# 05_-_Camera_Interface_2.net
KiCad netlist of a schematic drawn in Altium Designer
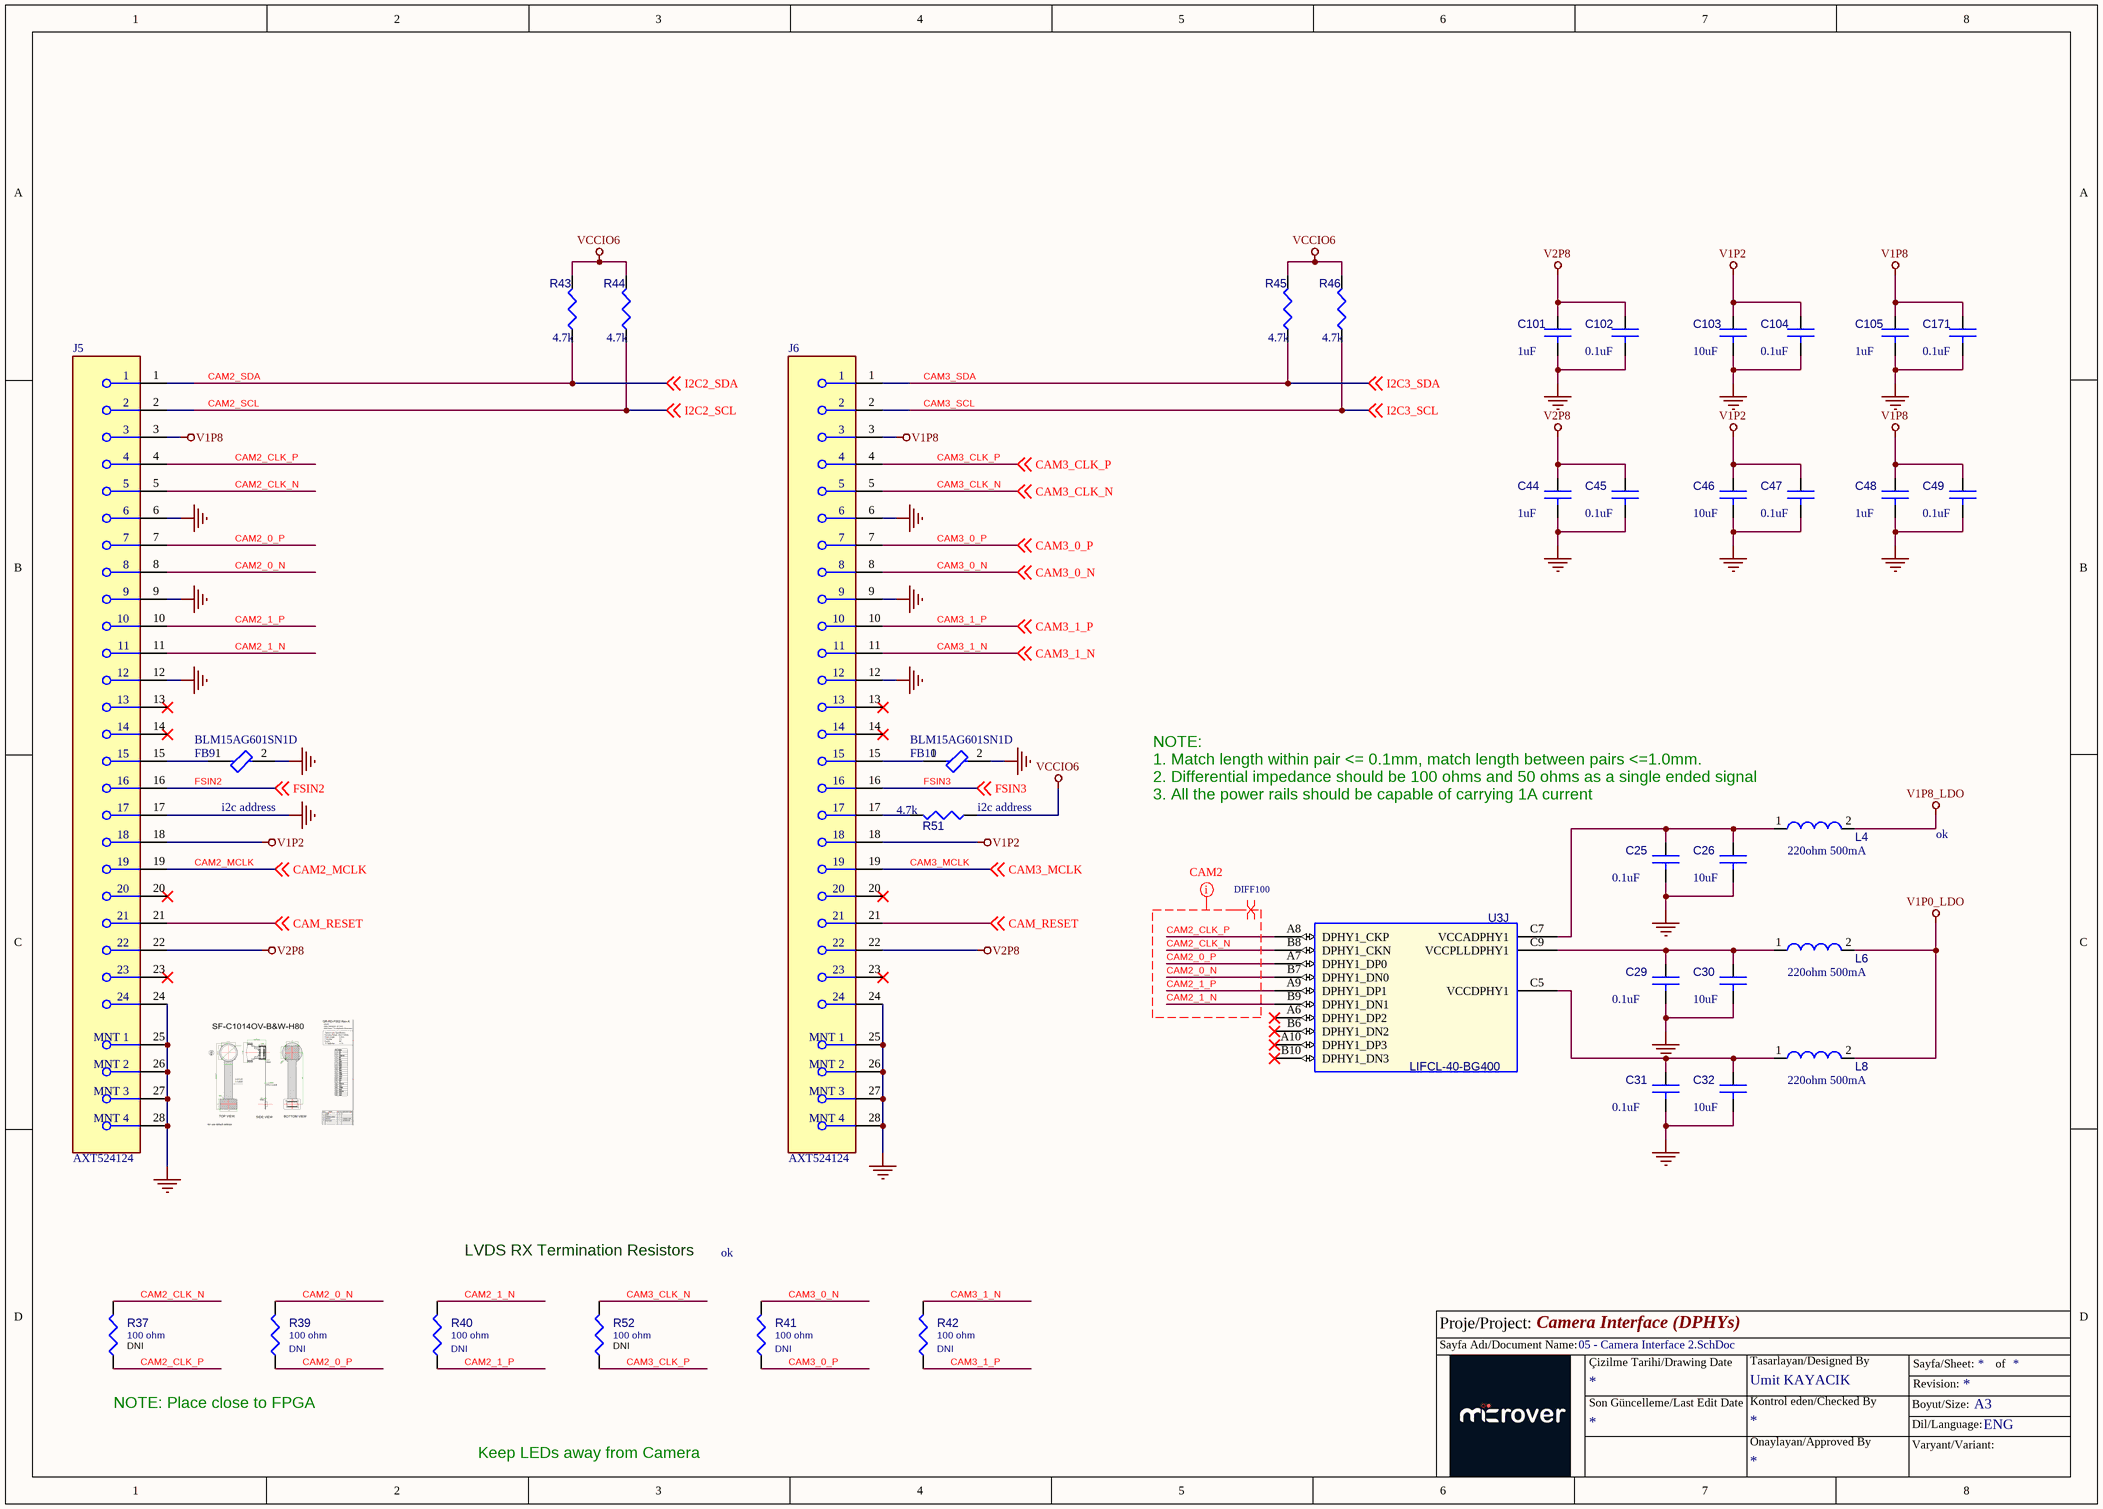
[diagram p0: 05 - Camera Interface 2.SchDoc]

(export (version "E")
  (design (tool "Eeschema 10.0.6"))
  (components
    (comp (ref "C25")
      (value "0.1uF")
      (footprint "C0201")
      (description "CAP CER 0.1UF 25V 10% X5R 0201")
      (fields
        (field (name "MANUFACTURER") "Murata")
        (field (name "MANUFACTURER PART NUMBER") "GRM033R61E104KE14J")
      )
      (libsource (lib "*") (part "0u1_0402"))
    )
    (comp (ref "C26")
      (value "10uF")
      (footprint "C0402")
      (description "CAP CER 10UF 10V X5R 0402")
      (fields
        (field (name "MANUFACTURER") "Samsung")
        (field (name "MANUFACTURER PART NUMBER") "CL05A106MP8NUB8")
      )
      (libsource (lib "*") (part "10uF_0603"))
    )
    (comp (ref "C29")
      (value "0.1uF")
      (footprint "C0201")
      (description "CAP CER 0.1UF 25V 10% X5R 0201")
      (fields
        (field (name "MANUFACTURER") "Murata")
        (field (name "MANUFACTURER PART NUMBER") "GRM033R61E104KE14J")
      )
      (libsource (lib "*") (part "0u1_0402"))
    )
    (comp (ref "C30")
      (value "10uF")
      (footprint "C0402")
      (description "CAP CER 10UF 10V X5R 0402")
      (fields
        (field (name "MANUFACTURER") "Samsung")
        (field (name "MANUFACTURER PART NUMBER") "CL05A106MP8NUB8")
      )
      (libsource (lib "*") (part "10uF_0603"))
    )
    (comp (ref "C31")
      (value "0.1uF")
      (footprint "C0201")
      (description "CAP CER 0.1UF 25V 10% X5R 0201")
      (fields
        (field (name "MANUFACTURER") "Murata")
        (field (name "MANUFACTURER PART NUMBER") "GRM033R61E104KE14J")
      )
      (libsource (lib "*") (part "0u1_0402"))
    )
    (comp (ref "C32")
      (value "10uF")
      (footprint "C0402")
      (description "CAP CER 10UF 10V X5R 0402")
      (fields
        (field (name "MANUFACTURER") "Samsung")
        (field (name "MANUFACTURER PART NUMBER") "CL05A106MP8NUB8")
      )
      (libsource (lib "*") (part "10uF_0603"))
    )
    (comp (ref "C44")
      (value "1uF")
      (footprint "C0603")
      (description "CAP CECAP CER 10UF 10V X5R 20% 0603")
      (fields
        (field (name "MANUFACTURER") "Taiyo Yuden")
        (field (name "MANUFACTURER PART NUMBER") "LMK107BJ106MALTD")
      )
      (libsource (lib "*") (part "10uF_0603"))
    )
    (comp (ref "C45")
      (value "0.1uF")
      (footprint "C0201")
      (description "CAP CER 0.1UF 25V 10% X5R 0201")
      (fields
        (field (name "MANUFACTURER") "Murata")
        (field (name "MANUFACTURER PART NUMBER") "GRM033R61E104KE14J")
      )
      (libsource (lib "*") (part "0u1_0402"))
    )
    (comp (ref "C46")
      (value "10uF")
      (footprint "C0603")
      (description "CAP CECAP CER 10UF 10V X5R 20% 0603")
      (fields
        (field (name "MANUFACTURER") "Taiyo Yuden")
        (field (name "MANUFACTURER PART NUMBER") "LMK107BJ106MALTD")
      )
      (libsource (lib "*") (part "10uF_0603"))
    )
    (comp (ref "C47")
      (value "0.1uF")
      (footprint "C0201")
      (description "CAP CER 0.1UF 25V 10% X5R 0201")
      (fields
        (field (name "MANUFACTURER") "Murata")
        (field (name "MANUFACTURER PART NUMBER") "GRM033R61E104KE14J")
      )
      (libsource (lib "*") (part "0u1_0402"))
    )
    (comp (ref "C48")
      (value "1uF")
      (footprint "C0603")
      (description "CAP CECAP CER 10UF 10V X5R 20% 0603")
      (fields
        (field (name "MANUFACTURER") "Taiyo Yuden")
        (field (name "MANUFACTURER PART NUMBER") "LMK107BJ106MALTD")
      )
      (libsource (lib "*") (part "10uF_0603"))
    )
    (comp (ref "C49")
      (value "0.1uF")
      (footprint "C0201")
      (description "CAP CER 0.1UF 25V 10% X5R 0201")
      (fields
        (field (name "MANUFACTURER") "Murata")
        (field (name "MANUFACTURER PART NUMBER") "GRM033R61E104KE14J")
      )
      (libsource (lib "*") (part "0u1_0402"))
    )
    (comp (ref "C101")
      (value "1uF")
      (footprint "C0603")
      (description "CAP CECAP CER 10UF 10V X5R 20% 0603")
      (fields
        (field (name "MANUFACTURER") "Taiyo Yuden")
        (field (name "MANUFACTURER PART NUMBER") "LMK107BJ106MALTD")
      )
      (libsource (lib "*") (part "10uF_0603"))
    )
    (comp (ref "C102")
      (value "0.1uF")
      (footprint "C0201")
      (description "CAP CER 0.1UF 25V 10% X5R 0201")
      (fields
        (field (name "MANUFACTURER") "Murata")
        (field (name "MANUFACTURER PART NUMBER") "GRM033R61E104KE14J")
      )
      (libsource (lib "*") (part "0u1_0402"))
    )
    (comp (ref "C103")
      (value "10uF")
      (footprint "C0603")
      (description "CAP CECAP CER 10UF 10V X5R 20% 0603")
      (fields
        (field (name "MANUFACTURER") "Taiyo Yuden")
        (field (name "MANUFACTURER PART NUMBER") "LMK107BJ106MALTD")
      )
      (libsource (lib "*") (part "10uF_0603"))
    )
    (comp (ref "C104")
      (value "0.1uF")
      (footprint "C0201")
      (description "CAP CER 0.1UF 25V 10% X5R 0201")
      (fields
        (field (name "MANUFACTURER") "Murata")
        (field (name "MANUFACTURER PART NUMBER") "GRM033R61E104KE14J")
      )
      (libsource (lib "*") (part "0u1_0402"))
    )
    (comp (ref "C105")
      (value "1uF")
      (footprint "C0603")
      (description "CAP CECAP CER 10UF 10V X5R 20% 0603")
      (fields
        (field (name "MANUFACTURER") "Taiyo Yuden")
        (field (name "MANUFACTURER PART NUMBER") "LMK107BJ106MALTD")
      )
      (libsource (lib "*") (part "10uF_0603"))
    )
    (comp (ref "C171")
      (value "0.1uF")
      (footprint "C0201")
      (description "CAP CER 0.1UF 25V 10% X5R 0201")
      (fields
        (field (name "MANUFACTURER") "Murata")
        (field (name "MANUFACTURER PART NUMBER") "GRM033R61E104KE14J")
      )
      (libsource (lib "*") (part "0u1_0402"))
    )
    (comp (ref "FB9")
      (value "BLM15AG601SN1D")
      (footprint "FP-BLM15-0_05-MFG")
      (description "Chip Ferrite Bead, 0402, 600Ω @ 100MHz, 0.52Ω, 25%, 300mA")
      (fields (field (name "TOLERANCE") "25%"))
      (libsource (lib "Altium Content Vault") (part "5f30dd21d616792df468990f7003faa"))
    )
    (comp (ref "FB10")
      (value "BLM15AG601SN1D")
      (footprint "FP-BLM15-0_05-MFG")
      (description "Chip Ferrite Bead, 0402, 600Ω @ 100MHz, 0.52Ω, 25%, 300mA")
      (fields (field (name "TOLERANCE") "25%"))
      (libsource (lib "Altium Content Vault") (part "5f30dd21d616792df468990f7003faa"))
    )
    (comp (ref "J5")
      (value "AXT524124")
      (footprint "FP-AXT524124-MFG")
      (description "AXT524124 24 Position 0.4 mm Pitch Dual Row Board to Board Socket Narrow Pitch Connector")
      (libsource (lib "Chronos") (part "AXT524124"))
    )
    (comp (ref "J6")
      (value "AXT524124")
      (footprint "FP-AXT524124-MFG")
      (description "AXT524124 24 Position 0.4 mm Pitch Dual Row Board to Board Socket Narrow Pitch Connector")
      (libsource (lib "Chronos") (part "AXT524124"))
    )
    (comp (ref "L4")
      (value "220ohm 500mA")
      (footprint "FB0402")
      (description "FERRITE BEAD 600 OHM 0402 1LN")
      (fields
        (field (name "MANUFACTURER") "Murata")
        (field (name "MANUFACTURER PART NUMBER") "BLM15AX601SN1D")
      )
      (libsource (lib "*") (part "FB0603"))
    )
    (comp (ref "L6")
      (value "220ohm 500mA")
      (footprint "FB0402")
      (description "FERRITE BEAD 600 OHM 0402 1LN")
      (fields
        (field (name "MANUFACTURER") "Murata")
        (field (name "MANUFACTURER PART NUMBER") "BLM15AX601SN1D")
      )
      (libsource (lib "*") (part "FB0603"))
    )
    (comp (ref "L8")
      (value "220ohm 500mA")
      (footprint "FB0402")
      (description "FERRITE BEAD 600 OHM 0402 1LN")
      (fields
        (field (name "MANUFACTURER") "Murata")
        (field (name "MANUFACTURER PART NUMBER") "BLM15AX601SN1D")
      )
      (libsource (lib "*") (part "FB0603"))
    )
    (comp (ref "R37")
      (value "100 ohm")
      (footprint "R0201")
      (description "RES SMD 100 OHM 1% 1/20W 0201")
      (fields (field (name "MFG") "Yageo") (field (name "MANUFACTURER PART NUMBER") "RC0201FR-07100RL"))
      (libsource (lib "*") (part "RES_100K_1W16_0402_5P"))
    )
    (comp (ref "R39")
      (value "100 ohm")
      (footprint "R0201")
      (description "RES SMD 100 OHM 1% 1/20W 0201")
      (fields
        (field (name "MFG") "Yageo")
        (field (name "MANUFACTURER PART NUMBER") "RC0201FR-07100RL")
        (field (name "ASSY") "DNI")
      )
      (libsource (lib "*") (part "RES_100K_1W16_0402_5P"))
    )
    (comp (ref "R40")
      (value "100 ohm")
      (footprint "R0201")
      (description "RES SMD 100 OHM 1% 1/20W 0201")
      (fields
        (field (name "MFG") "Yageo")
        (field (name "MANUFACTURER PART NUMBER") "RC0201FR-07100RL")
        (field (name "ASSY") "DNI")
      )
      (libsource (lib "*") (part "RES_100K_1W16_0402_5P"))
    )
    (comp (ref "R41")
      (value "100 ohm")
      (footprint "R0201")
      (description "RES SMD 100 OHM 1% 1/20W 0201")
      (fields
        (field (name "MFG") "Yageo")
        (field (name "ASSY") "DNI")
        (field (name "MANUFACTURER PART NUMBER") "RC0201FR-07100RL")
      )
      (libsource (lib "*") (part "RES_100K_1W16_0402_5P"))
    )
    (comp (ref "R42")
      (value "100 ohm")
      (footprint "R0201")
      (description "RES SMD 100 OHM 1% 1/20W 0201")
      (fields
        (field (name "MFG") "Yageo")
        (field (name "ASSY") "DNI")
        (field (name "MANUFACTURER PART NUMBER") "RC0201FR-07100RL")
      )
      (libsource (lib "*") (part "RES_100K_1W16_0402_5P"))
    )
    (comp (ref "R43")
      (value "4.7k")
      (footprint "R0402")
      (description "RES SMD 2.2K OHM 1% 1/10W 0402")
      (fields
        (field (name "MANUFACTURER PART NUMBER") "ERJ-2RKF2201X")
        (field (name "MANUFACTURER") "Panasonic")
      )
      (libsource (lib "*") (part "5k1_0402"))
    )
    (comp (ref "R44")
      (value "4.7k")
      (footprint "R0402")
      (description "RES SMD 2.2K OHM 1% 1/10W 0402")
      (fields
        (field (name "MANUFACTURER PART NUMBER") "ERJ-2RKF2201X")
        (field (name "MANUFACTURER") "Panasonic")
      )
      (libsource (lib "*") (part "5k1_0402"))
    )
    (comp (ref "R45")
      (value "4.7k")
      (footprint "R0402")
      (description "RES SMD 2.2K OHM 1% 1/10W 0402")
      (fields
        (field (name "MANUFACTURER PART NUMBER") "ERJ-2RKF2201X")
        (field (name "MANUFACTURER") "Panasonic")
      )
      (libsource (lib "*") (part "5k1_0402"))
    )
    (comp (ref "R46")
      (value "4.7k")
      (footprint "R0402")
      (description "RES SMD 2.2K OHM 1% 1/10W 0402")
      (fields
        (field (name "MANUFACTURER PART NUMBER") "ERJ-2RKF2201X")
        (field (name "MANUFACTURER") "Panasonic")
      )
      (libsource (lib "*") (part "5k1_0402"))
    )
    (comp (ref "R51")
      (value "4.7k")
      (footprint "R0402")
      (description "RES SMD 2.2K OHM 1% 1/10W 0402")
      (fields
        (field (name "MANUFACTURER PART NUMBER") "ERJ-2RKF2201X")
        (field (name "MANUFACTURER") "Panasonic")
      )
      (libsource (lib "*") (part "5k1_0402"))
    )
    (comp (ref "R52")
      (value "100 ohm")
      (footprint "R0201")
      (description "RES SMD 100 OHM 1% 1/20W 0201")
      (fields (field (name "MFG") "Yageo") (field (name "MANUFACTURER PART NUMBER") "RC0201FR-07100RL"))
      (libsource (lib "*") (part "RES_100K_1W16_0402_5P"))
    )
    (comp (ref "U3")
      (value "LIFCL-40-BG400")
      (footprint "LIFCL-40-BG400")
      (libsource (lib "*") (part "LIFCL-40-BG400"))
    )
  )
  (nets
    (net (code "1") (name "/CAM2_0_N") (class "Default")
      (node (ref "J5") (pin "8") (pinfunction "8_8") (pintype "passive"))
      (node (ref "R39") (pin "2") (pinfunction "2_2") (pintype "passive"))
      (node (ref "U3") (pin "B7") (pinfunction "DPHY1_DN0_B7") (pintype "bidirectional"))
    )
    (net (code "2") (name "/CAM2_0_P") (class "Default")
      (node (ref "J5") (pin "7") (pinfunction "7_7") (pintype "passive"))
      (node (ref "R39") (pin "1") (pinfunction "1_1") (pintype "passive"))
      (node (ref "U3") (pin "A7") (pinfunction "DPHY1_DP0_A7") (pintype "bidirectional"))
    )
    (net (code "3") (name "/CAM2_1_N") (class "Default")
      (node (ref "J5") (pin "11") (pinfunction "11_11") (pintype "passive"))
      (node (ref "R40") (pin "2") (pinfunction "2_2") (pintype "passive"))
      (node (ref "U3") (pin "B9") (pinfunction "DPHY1_DN1_B9") (pintype "bidirectional"))
    )
    (net (code "4") (name "/CAM2_1_P") (class "Default")
      (node (ref "J5") (pin "10") (pinfunction "10_10") (pintype "passive"))
      (node (ref "R40") (pin "1") (pinfunction "1_1") (pintype "passive"))
      (node (ref "U3") (pin "A9") (pinfunction "DPHY1_DP1_A9") (pintype "bidirectional"))
    )
    (net (code "5") (name "/CAM2_CLK_N") (class "Default")
      (node (ref "J5") (pin "5") (pinfunction "5_5") (pintype "passive"))
      (node (ref "R37") (pin "2") (pinfunction "2_2") (pintype "passive"))
      (node (ref "U3") (pin "B8") (pinfunction "DPHY1_CKN_B8") (pintype "bidirectional"))
    )
    (net (code "6") (name "/CAM2_CLK_P") (class "Default")
      (node (ref "J5") (pin "4") (pinfunction "4_4") (pintype "passive"))
      (node (ref "R37") (pin "1") (pinfunction "1_1") (pintype "passive"))
      (node (ref "U3") (pin "A8") (pinfunction "DPHY1_CKP_A8") (pintype "bidirectional"))
    )
    (net (code "7") (name "CAM2_MCLK") (class "Default")
      (node (ref "J5") (pin "19") (pinfunction "19_19") (pintype "passive"))
    )
    (net (code "8") (name "CAM3_0_N") (class "Default")
      (node (ref "J6") (pin "8") (pinfunction "8_8") (pintype "passive"))
      (node (ref "R41") (pin "2") (pinfunction "2_2") (pintype "passive"))
    )
    (net (code "9") (name "CAM3_0_P") (class "Default")
      (node (ref "J6") (pin "7") (pinfunction "7_7") (pintype "passive"))
      (node (ref "R41") (pin "1") (pinfunction "1_1") (pintype "passive"))
    )
    (net (code "10") (name "CAM3_1_N") (class "Default")
      (node (ref "J6") (pin "11") (pinfunction "11_11") (pintype "passive"))
      (node (ref "R42") (pin "2") (pinfunction "2_2") (pintype "passive"))
    )
    (net (code "11") (name "CAM3_1_P") (class "Default")
      (node (ref "J6") (pin "10") (pinfunction "10_10") (pintype "passive"))
      (node (ref "R42") (pin "1") (pinfunction "1_1") (pintype "passive"))
    )
    (net (code "12") (name "CAM3_CLK_N") (class "Default")
      (node (ref "J6") (pin "5") (pinfunction "5_5") (pintype "passive"))
      (node (ref "R52") (pin "2") (pinfunction "2_2") (pintype "passive"))
    )
    (net (code "13") (name "CAM3_CLK_P") (class "Default")
      (node (ref "J6") (pin "4") (pinfunction "4_4") (pintype "passive"))
      (node (ref "R52") (pin "1") (pinfunction "1_1") (pintype "passive"))
    )
    (net (code "14") (name "CAM3_MCLK") (class "Default")
      (node (ref "J6") (pin "19") (pinfunction "19_19") (pintype "passive"))
    )
    (net (code "15") (name "CAM_RESET") (class "Default")
      (node (ref "J5") (pin "21") (pinfunction "21_21") (pintype "passive"))
      (node (ref "J6") (pin "21") (pinfunction "21_21") (pintype "passive"))
    )
    (net (code "16") (name "FSIN2") (class "Default")
      (node (ref "J5") (pin "16") (pinfunction "16_16") (pintype "passive"))
    )
    (net (code "17") (name "FSIN3") (class "Default")
      (node (ref "J6") (pin "16") (pinfunction "16_16") (pintype "passive"))
    )
    (net (code "18") (name "GND") (class "Default")
      (node (ref "C101") (pin "2") (pinfunction "2_2") (pintype "passive"))
      (node (ref "C102") (pin "2") (pinfunction "2_2") (pintype "passive"))
      (node (ref "C103") (pin "2") (pinfunction "2_2") (pintype "passive"))
      (node (ref "C104") (pin "2") (pinfunction "2_2") (pintype "passive"))
      (node (ref "C105") (pin "2") (pinfunction "2_2") (pintype "passive"))
      (node (ref "C171") (pin "2") (pinfunction "2_2") (pintype "passive"))
      (node (ref "C25") (pin "2") (pinfunction "2_2") (pintype "passive"))
      (node (ref "C26") (pin "2") (pinfunction "2_2") (pintype "passive"))
      (node (ref "C29") (pin "2") (pinfunction "2_2") (pintype "passive"))
      (node (ref "C30") (pin "2") (pinfunction "2_2") (pintype "passive"))
      (node (ref "C31") (pin "2") (pinfunction "2_2") (pintype "passive"))
      (node (ref "C32") (pin "2") (pinfunction "2_2") (pintype "passive"))
      (node (ref "C44") (pin "2") (pinfunction "2_2") (pintype "passive"))
      (node (ref "C45") (pin "2") (pinfunction "2_2") (pintype "passive"))
      (node (ref "C46") (pin "2") (pinfunction "2_2") (pintype "passive"))
      (node (ref "C47") (pin "2") (pinfunction "2_2") (pintype "passive"))
      (node (ref "C48") (pin "2") (pinfunction "2_2") (pintype "passive"))
      (node (ref "C49") (pin "2") (pinfunction "2_2") (pintype "passive"))
      (node (ref "FB10") (pin "2") (pinfunction "2_2") (pintype "passive"))
      (node (ref "FB9") (pin "2") (pinfunction "2_2") (pintype "passive"))
      (node (ref "J5") (pin "12") (pinfunction "12_12") (pintype "passive"))
      (node (ref "J5") (pin "17") (pinfunction "17_17") (pintype "passive"))
      (node (ref "J5") (pin "24") (pinfunction "24_24") (pintype "passive"))
      (node (ref "J5") (pin "25") (pinfunction "MNT_1_25") (pintype "passive"))
      (node (ref "J5") (pin "26") (pinfunction "MNT_2_26") (pintype "passive"))
      (node (ref "J5") (pin "27") (pinfunction "MNT_3_27") (pintype "passive"))
      (node (ref "J5") (pin "28") (pinfunction "MNT_4_28") (pintype "passive"))
      (node (ref "J5") (pin "6") (pinfunction "6_6") (pintype "passive"))
      (node (ref "J5") (pin "9") (pinfunction "9_9") (pintype "passive"))
      (node (ref "J6") (pin "12") (pinfunction "12_12") (pintype "passive"))
      (node (ref "J6") (pin "24") (pinfunction "24_24") (pintype "passive"))
      (node (ref "J6") (pin "25") (pinfunction "MNT_1_25") (pintype "passive"))
      (node (ref "J6") (pin "26") (pinfunction "MNT_2_26") (pintype "passive"))
      (node (ref "J6") (pin "27") (pinfunction "MNT_3_27") (pintype "passive"))
      (node (ref "J6") (pin "28") (pinfunction "MNT_4_28") (pintype "passive"))
      (node (ref "J6") (pin "6") (pinfunction "6_6") (pintype "passive"))
      (node (ref "J6") (pin "9") (pinfunction "9_9") (pintype "passive"))
    )
    (net (code "19") (name "I2C2_SCL") (class "Default")
      (node (ref "J5") (pin "2") (pinfunction "2_2") (pintype "passive"))
      (node (ref "R44") (pin "2") (pinfunction "2_2") (pintype "passive"))
    )
    (net (code "20") (name "I2C2_SDA") (class "Default")
      (node (ref "J5") (pin "1") (pinfunction "1_1") (pintype "passive"))
      (node (ref "R43") (pin "2") (pinfunction "2_2") (pintype "passive"))
    )
    (net (code "21") (name "I2C3_SCL") (class "Default")
      (node (ref "J6") (pin "2") (pinfunction "2_2") (pintype "passive"))
      (node (ref "R46") (pin "2") (pinfunction "2_2") (pintype "passive"))
    )
    (net (code "22") (name "I2C3_SDA") (class "Default")
      (node (ref "J6") (pin "1") (pinfunction "1_1") (pintype "passive"))
      (node (ref "R45") (pin "2") (pinfunction "2_2") (pintype "passive"))
    )
    (net (code "23") (name "Net-(FB9-Pad1)") (class "Default")
      (node (ref "FB9") (pin "1") (pinfunction "1_1") (pintype "passive"))
      (node (ref "J5") (pin "15") (pinfunction "15_15") (pintype "passive"))
    )
    (net (code "24") (name "Net-(FB10-Pad1)") (class "Default")
      (node (ref "FB10") (pin "1") (pinfunction "1_1") (pintype "passive"))
      (node (ref "J6") (pin "15") (pinfunction "15_15") (pintype "passive"))
    )
    (net (code "25") (name "Net-(J6-Pad17)") (class "Default")
      (node (ref "J6") (pin "17") (pinfunction "17_17") (pintype "passive"))
      (node (ref "R51") (pin "1") (pinfunction "1_1") (pintype "passive"))
    )
    (net (code "26") (name "Net-(U3J-VCCADPHY1)") (class "Default")
      (node (ref "C25") (pin "1") (pinfunction "1_1") (pintype "passive"))
      (node (ref "C26") (pin "1") (pinfunction "1_1") (pintype "passive"))
      (node (ref "L4") (pin "1") (pinfunction "1_1") (pintype "passive"))
      (node (ref "U3") (pin "C7") (pinfunction "VCCADPHY1_C7") (pintype "power_in"))
    )
    (net (code "27") (name "Net-(U3J-VCCDPHY1)") (class "Default")
      (node (ref "C31") (pin "1") (pinfunction "1_1") (pintype "passive"))
      (node (ref "C32") (pin "1") (pinfunction "1_1") (pintype "passive"))
      (node (ref "L8") (pin "1") (pinfunction "1_1") (pintype "passive"))
      (node (ref "U3") (pin "C5") (pinfunction "VCCDPHY1_C5") (pintype "power_in"))
    )
    (net (code "28") (name "Net-(U3J-VCCPLLDPHY1)") (class "Default")
      (node (ref "C29") (pin "1") (pinfunction "1_1") (pintype "passive"))
      (node (ref "C30") (pin "1") (pinfunction "1_1") (pintype "passive"))
      (node (ref "L6") (pin "1") (pinfunction "1_1") (pintype "passive"))
      (node (ref "U3") (pin "C9") (pinfunction "VCCPLLDPHY1_C9") (pintype "power_in"))
    )
    (net (code "29") (name "V1P0_LDO") (class "Default")
      (node (ref "L6") (pin "2") (pinfunction "2_2") (pintype "passive"))
      (node (ref "L8") (pin "2") (pinfunction "2_2") (pintype "passive"))
    )
    (net (code "30") (name "V1P2") (class "Default")
      (node (ref "C103") (pin "1") (pinfunction "1_1") (pintype "passive"))
      (node (ref "C104") (pin "1") (pinfunction "1_1") (pintype "passive"))
      (node (ref "C46") (pin "1") (pinfunction "1_1") (pintype "passive"))
      (node (ref "C47") (pin "1") (pinfunction "1_1") (pintype "passive"))
      (node (ref "J5") (pin "18") (pinfunction "18_18") (pintype "passive"))
      (node (ref "J6") (pin "18") (pinfunction "18_18") (pintype "passive"))
    )
    (net (code "31") (name "V1P8") (class "Default")
      (node (ref "C105") (pin "1") (pinfunction "1_1") (pintype "passive"))
      (node (ref "C171") (pin "1") (pinfunction "1_1") (pintype "passive"))
      (node (ref "C48") (pin "1") (pinfunction "1_1") (pintype "passive"))
      (node (ref "C49") (pin "1") (pinfunction "1_1") (pintype "passive"))
      (node (ref "J5") (pin "3") (pinfunction "3_3") (pintype "passive"))
      (node (ref "J6") (pin "3") (pinfunction "3_3") (pintype "passive"))
    )
    (net (code "32") (name "V1P8_LDO") (class "Default")
      (node (ref "L4") (pin "2") (pinfunction "2_2") (pintype "passive"))
    )
    (net (code "33") (name "V2P8") (class "Default")
      (node (ref "C101") (pin "1") (pinfunction "1_1") (pintype "passive"))
      (node (ref "C102") (pin "1") (pinfunction "1_1") (pintype "passive"))
      (node (ref "C44") (pin "1") (pinfunction "1_1") (pintype "passive"))
      (node (ref "C45") (pin "1") (pinfunction "1_1") (pintype "passive"))
      (node (ref "J5") (pin "22") (pinfunction "22_22") (pintype "passive"))
      (node (ref "J6") (pin "22") (pinfunction "22_22") (pintype "passive"))
    )
    (net (code "34") (name "VCCIO6") (class "Default")
      (node (ref "R43") (pin "1") (pinfunction "1_1") (pintype "passive"))
      (node (ref "R44") (pin "1") (pinfunction "1_1") (pintype "passive"))
      (node (ref "R45") (pin "1") (pinfunction "1_1") (pintype "passive"))
      (node (ref "R46") (pin "1") (pinfunction "1_1") (pintype "passive"))
      (node (ref "R51") (pin "2") (pinfunction "2_2") (pintype "passive"))
    )
    (net (code "35") (name "unconnected-(J5-Pad13)") (class "Default")
      (node (ref "J5") (pin "13") (pinfunction "13_13") (pintype "passive+no_connect"))
    )
    (net (code "36") (name "unconnected-(J5-Pad14)") (class "Default")
      (node (ref "J5") (pin "14") (pinfunction "14_14") (pintype "passive+no_connect"))
    )
    (net (code "37") (name "unconnected-(J5-Pad20)") (class "Default")
      (node (ref "J5") (pin "20") (pinfunction "20_20") (pintype "passive+no_connect"))
    )
    (net (code "38") (name "unconnected-(J5-Pad23)") (class "Default")
      (node (ref "J5") (pin "23") (pinfunction "23_23") (pintype "passive+no_connect"))
    )
    (net (code "39") (name "unconnected-(J6-Pad13)") (class "Default")
      (node (ref "J6") (pin "13") (pinfunction "13_13") (pintype "passive+no_connect"))
    )
    (net (code "40") (name "unconnected-(J6-Pad14)") (class "Default")
      (node (ref "J6") (pin "14") (pinfunction "14_14") (pintype "passive+no_connect"))
    )
    (net (code "41") (name "unconnected-(J6-Pad20)") (class "Default")
      (node (ref "J6") (pin "20") (pinfunction "20_20") (pintype "passive+no_connect"))
    )
    (net (code "42") (name "unconnected-(J6-Pad23)") (class "Default")
      (node (ref "J6") (pin "23") (pinfunction "23_23") (pintype "passive+no_connect"))
    )
    (net (code "43") (name "unconnected-(U3J-DPHY1_DN2-PadB6)") (class "Default")
      (node (ref "U3") (pin "B6") (pinfunction "DPHY1_DN2_B6") (pintype "bidirectional+no_connect"))
    )
    (net (code "44") (name "unconnected-(U3J-DPHY1_DN3-PadB10)") (class "Default")
      (node (ref "U3") (pin "B10") (pinfunction "DPHY1_DN3_B10") (pintype "bidirectional+no_connect"))
    )
    (net (code "45") (name "unconnected-(U3J-DPHY1_DP2-PadA6)") (class "Default")
      (node (ref "U3") (pin "A6") (pinfunction "DPHY1_DP2_A6") (pintype "bidirectional+no_connect"))
    )
    (net (code "46") (name "unconnected-(U3J-DPHY1_DP3-PadA10)") (class "Default")
      (node (ref "U3") (pin "A10") (pinfunction "DPHY1_DP3_A10") (pintype "bidirectional+no_connect"))
    )
  )
)
